# ATmega32_ComServ.net
KiCad netlist of a schematic drawn in Altium Designer
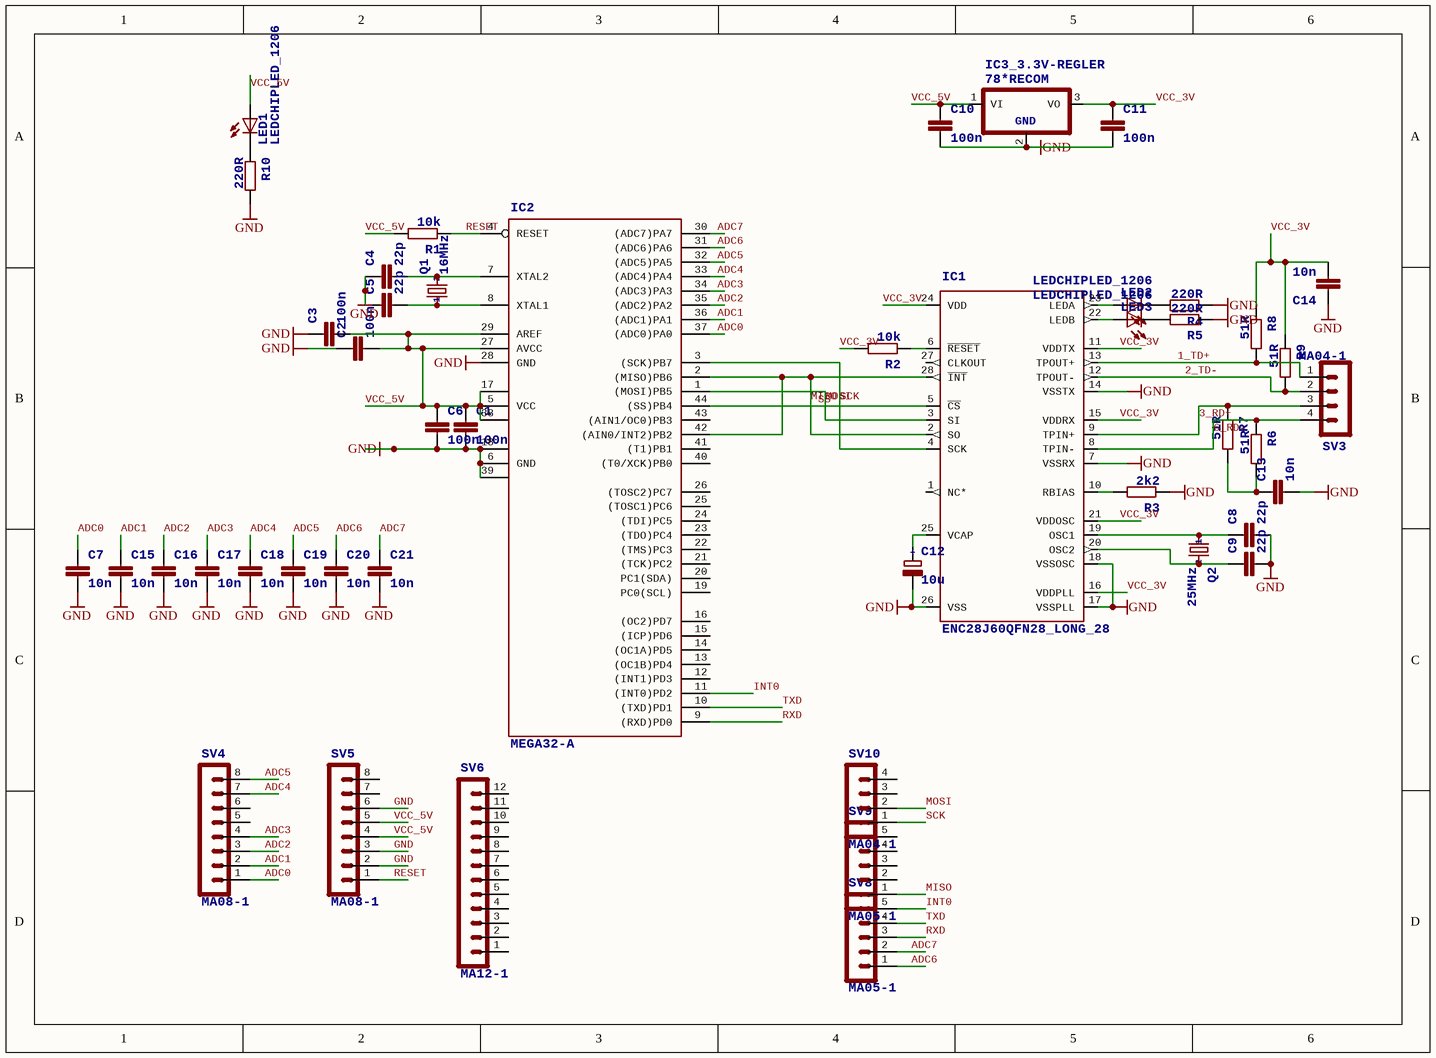
[diagram p0: ATmega32_ComServ.SchDoc]

(export (version "E")
  (design (tool "Eeschema 10.0.6"))
  (components
    (comp (ref "C1")
      (value "100n")
      (footprint "C0805")
      (description "<B>CAPACITOR</B>, European symbol")
      (libsource (lib "rcl") (part "C-EUC0805"))
    )
    (comp (ref "C2")
      (value "100n")
      (footprint "C0805")
      (description "<B>CAPACITOR</B>, European symbol")
      (libsource (lib "") (part "C-EUC0805_1"))
    )
    (comp (ref "C3")
      (value "100n")
      (footprint "C0805")
      (description "<B>CAPACITOR</B>, European symbol")
      (libsource (lib "") (part "C-EUC0805_1"))
    )
    (comp (ref "C4")
      (value "22p")
      (footprint "C0805")
      (description "<B>CAPACITOR</B>, European symbol")
      (libsource (lib "") (part "C-EUC0805_1"))
    )
    (comp (ref "C5")
      (value "22p")
      (footprint "C0805")
      (description "<B>CAPACITOR</B>, European symbol")
      (libsource (lib "") (part "C-EUC0805_1"))
    )
    (comp (ref "C6")
      (value "100n")
      (footprint "C0805")
      (description "<B>CAPACITOR</B>, European symbol")
      (libsource (lib "rcl") (part "C-EUC0805"))
    )
    (comp (ref "C7")
      (value "10n")
      (footprint "C0805")
      (description "<B>CAPACITOR</B>, European symbol")
      (libsource (lib "rcl") (part "C-EUC0805"))
    )
    (comp (ref "C8")
      (value "22p")
      (footprint "C0805")
      (description "<B>CAPACITOR</B>, European symbol")
      (libsource (lib "") (part "C-EUC0805_1"))
    )
    (comp (ref "C9")
      (value "22p")
      (footprint "C0805")
      (description "<B>CAPACITOR</B>, European symbol")
      (libsource (lib "") (part "C-EUC0805_1"))
    )
    (comp (ref "C10")
      (value "100n")
      (footprint "C0805")
      (description "<B>CAPACITOR</B>, European symbol")
      (libsource (lib "rcl") (part "C-EUC0805"))
    )
    (comp (ref "C11")
      (value "100n")
      (footprint "C0805")
      (description "<B>CAPACITOR</B>, European symbol")
      (libsource (lib "rcl") (part "C-EUC0805"))
    )
    (comp (ref "C12")
      (value "10u")
      (footprint "SMC_D")
      (description "<B>POLARIZED CAPACITOR</B>, European symbol")
      (fields (field (name "+") "+"))
      (libsource (lib "rcl") (part "CPOL-EUSMCD"))
    )
    (comp (ref "C13")
      (value "10n")
      (footprint "C0805")
      (description "<B>CAPACITOR</B>, European symbol")
      (libsource (lib "") (part "C-EUC0805_1"))
    )
    (comp (ref "C14")
      (value "10n")
      (footprint "C0805")
      (description "<B>CAPACITOR</B>, European symbol")
      (libsource (lib "") (part "C-EUC0805_2"))
    )
    (comp (ref "C15")
      (value "10n")
      (footprint "C0805")
      (description "<B>CAPACITOR</B>, European symbol")
      (libsource (lib "rcl") (part "C-EUC0805"))
    )
    (comp (ref "C16")
      (value "10n")
      (footprint "C0805")
      (description "<B>CAPACITOR</B>, European symbol")
      (libsource (lib "rcl") (part "C-EUC0805"))
    )
    (comp (ref "C17")
      (value "10n")
      (footprint "C0805")
      (description "<B>CAPACITOR</B>, European symbol")
      (libsource (lib "rcl") (part "C-EUC0805"))
    )
    (comp (ref "C18")
      (value "10n")
      (footprint "C0805")
      (description "<B>CAPACITOR</B>, European symbol")
      (libsource (lib "rcl") (part "C-EUC0805"))
    )
    (comp (ref "C19")
      (value "10n")
      (footprint "C0805")
      (description "<B>CAPACITOR</B>, European symbol")
      (libsource (lib "rcl") (part "C-EUC0805"))
    )
    (comp (ref "C20")
      (value "10n")
      (footprint "C0805")
      (description "<B>CAPACITOR</B>, European symbol")
      (libsource (lib "rcl") (part "C-EUC0805"))
    )
    (comp (ref "C21")
      (value "10n")
      (footprint "C0805")
      (description "<B>CAPACITOR</B>, European symbol")
      (libsource (lib "rcl") (part "C-EUC0805"))
    )
    (comp (ref "IC1")
      (value "ENC28J60QFN28_LONG_28")
      (footprint "QFN28_LONG_ERRLES")
      (libsource (lib "microchip") (part "ENC28J60QFN28_LONG_28"))
    )
    (comp (ref "IC2") (value "MEGA32-A") (footprint "TQFP44") (libsource (lib "atmel") (part "MEGA32-A")))
    (comp (ref "IC3_3.3V-REGLER")
      (value "78*RECOM")
      (footprint "RECOM_3POL")
      (fields (field (name "GND") "GND"))
      (libsource (lib "linear") (part "78*RECOM"))
    )
    (comp (ref "LED1")
      (value "LEDCHIPLED_1206")
      (footprint "CHIPLED_1206")
      (libsource (lib "led") (part "LEDCHIPLED_1206"))
    )
    (comp (ref "LED2")
      (value "LEDCHIPLED_1206")
      (footprint "CHIPLED_1206")
      (libsource (lib "led") (part "LEDCHIPLED_1206"))
    )
    (comp (ref "LED3")
      (value "LEDCHIPLED_1206")
      (footprint "CHIPLED_1206")
      (libsource (lib "led") (part "LEDCHIPLED_1206"))
    )
    (comp (ref "Q1")
      (value "16MHz")
      (footprint "HC49/S")
      (description "<b>CRYSTAL</b>")
      (fields (field (name "1") "1") (field (name "2") "2"))
      (libsource (lib "crystal") (part "CRYSTALHC49S"))
    )
    (comp (ref "Q2")
      (value "25MHz")
      (footprint "HC49/S")
      (description "<b>CRYSTAL</b>")
      (fields (field (name "1") "1") (field (name "2") "2"))
      (libsource (lib "crystal") (part "CRYSTALHC49S"))
    )
    (comp (ref "R1")
      (value "10k")
      (footprint "R1206")
      (description "<B>RESISTOR</B>, European symbol")
      (libsource (lib "rcl") (part "R-EU_R1206"))
    )
    (comp (ref "R2")
      (value "10k")
      (footprint "R1206")
      (description "<B>RESISTOR</B>, European symbol")
      (libsource (lib "rcl") (part "R-EU_R1206"))
    )
    (comp (ref "R3")
      (value "2k2")
      (footprint "R1206")
      (description "<B>RESISTOR</B>, European symbol")
      (libsource (lib "rcl") (part "R-EU_R1206"))
    )
    (comp (ref "R4")
      (value "220R")
      (footprint "R1206")
      (description "<B>RESISTOR</B>, European symbol")
      (libsource (lib "rcl") (part "R-EU_R1206"))
    )
    (comp (ref "R5")
      (value "220R")
      (footprint "R1206")
      (description "<B>RESISTOR</B>, European symbol")
      (libsource (lib "rcl") (part "R-EU_R1206"))
    )
    (comp (ref "R6")
      (value "51R")
      (footprint "R0805")
      (description "<B>RESISTOR</B>, European symbol")
      (libsource (lib "rcl") (part "R-EU_R0805"))
    )
    (comp (ref "R7")
      (value "51R")
      (footprint "R1206")
      (description "<B>RESISTOR</B>, European symbol")
      (libsource (lib "rcl") (part "R-EU_R1206"))
    )
    (comp (ref "R8")
      (value "51R")
      (footprint "R0805")
      (description "<B>RESISTOR</B>, European symbol")
      (libsource (lib "rcl") (part "R-EU_R0805"))
    )
    (comp (ref "R9")
      (value "51R")
      (footprint "R0805")
      (description "<B>RESISTOR</B>, European symbol")
      (libsource (lib "rcl") (part "R-EU_R0805"))
    )
    (comp (ref "R10")
      (value "220R")
      (footprint "R1206")
      (description "<B>RESISTOR</B>, European symbol")
      (libsource (lib "rcl") (part "R-EU_R1206"))
    )
    (comp (ref "SV3")
      (value "MA04-1")
      (footprint "MA04-1")
      (description "<b>PIN HEADER</b>")
      (libsource (lib "con-lstb") (part "MA04-1"))
    )
    (comp (ref "SV4")
      (value "MA08-1")
      (footprint "MA08-1")
      (description "<b>PIN HEADER</b>")
      (libsource (lib "con-lstb") (part "MA08-1"))
    )
    (comp (ref "SV5")
      (value "MA08-1")
      (footprint "MA08-1")
      (description "<b>PIN HEADER</b>")
      (libsource (lib "con-lstb") (part "MA08-1"))
    )
    (comp (ref "SV6")
      (value "MA12-1")
      (footprint "MA12-1")
      (description "<b>PIN HEADER</b>")
      (libsource (lib "con-lstb") (part "MA12-1"))
    )
    (comp (ref "SV8")
      (value "MA05-1")
      (footprint "MA05-1")
      (description "<b>PIN HEADER</b>")
      (libsource (lib "con-lstb") (part "MA05-1"))
    )
    (comp (ref "SV9")
      (value "MA05-1")
      (footprint "MA05-1")
      (description "<b>PIN HEADER</b>")
      (libsource (lib "con-lstb") (part "MA05-1"))
    )
    (comp (ref "SV10")
      (value "MA04-1")
      (footprint "MA04-1")
      (description "<b>PIN HEADER</b>")
      (libsource (lib "con-lstb") (part "MA04-1"))
    )
  )
  (nets
    (net (code "1") (name "/1_TD+") (class "Default")
      (node (ref "IC1") (pin "13") (pinfunction "TPOUT+_13") (pintype "output"))
      (node (ref "R8") (pin "2") (pinfunction "2_2") (pintype "passive"))
      (node (ref "SV3") (pin "1") (pinfunction "1_1") (pintype "passive"))
    )
    (net (code "2") (name "/2_TD-") (class "Default")
      (node (ref "IC1") (pin "12") (pinfunction "TPOUT-_12") (pintype "output"))
      (node (ref "R9") (pin "2") (pinfunction "2_2") (pintype "passive"))
      (node (ref "SV3") (pin "2") (pinfunction "2_2") (pintype "passive"))
    )
    (net (code "3") (name "/3_RD+") (class "Default")
      (node (ref "IC1") (pin "9") (pinfunction "TPIN+_9") (pintype "passive"))
      (node (ref "R7") (pin "1") (pinfunction "1_1") (pintype "passive"))
      (node (ref "SV3") (pin "3") (pinfunction "3_3") (pintype "passive"))
    )
    (net (code "4") (name "/6_RD-") (class "Default")
      (node (ref "IC1") (pin "8") (pinfunction "TPIN-_8") (pintype "passive"))
      (node (ref "R6") (pin "1") (pinfunction "1_1") (pintype "passive"))
      (node (ref "SV3") (pin "4") (pinfunction "4_4") (pintype "passive"))
    )
    (net (code "5") (name "/ADC0") (class "Default")
      (node (ref "C7") (pin "1") (pinfunction "1_1") (pintype "passive"))
      (node (ref "IC2") (pin "37") (pinfunction "(ADC0)PA0_37") (pintype "passive"))
      (node (ref "SV4") (pin "1") (pinfunction "1_1") (pintype "passive"))
    )
    (net (code "6") (name "/ADC1") (class "Default")
      (node (ref "C15") (pin "1") (pinfunction "1_1") (pintype "passive"))
      (node (ref "IC2") (pin "36") (pinfunction "(ADC1)PA1_36") (pintype "passive"))
      (node (ref "SV4") (pin "2") (pinfunction "2_2") (pintype "passive"))
    )
    (net (code "7") (name "/ADC2") (class "Default")
      (node (ref "C16") (pin "1") (pinfunction "1_1") (pintype "passive"))
      (node (ref "IC2") (pin "35") (pinfunction "(ADC2)PA2_35") (pintype "passive"))
      (node (ref "SV4") (pin "3") (pinfunction "3_3") (pintype "passive"))
    )
    (net (code "8") (name "/ADC3") (class "Default")
      (node (ref "C17") (pin "1") (pinfunction "1_1") (pintype "passive"))
      (node (ref "IC2") (pin "34") (pinfunction "(ADC3)PA3_34") (pintype "passive"))
      (node (ref "SV4") (pin "4") (pinfunction "4_4") (pintype "passive"))
    )
    (net (code "9") (name "/ADC4") (class "Default")
      (node (ref "C18") (pin "1") (pinfunction "1_1") (pintype "passive"))
      (node (ref "IC2") (pin "33") (pinfunction "(ADC4)PA4_33") (pintype "passive"))
      (node (ref "SV4") (pin "7") (pinfunction "7_7") (pintype "passive"))
    )
    (net (code "10") (name "/ADC5") (class "Default")
      (node (ref "C19") (pin "1") (pinfunction "1_1") (pintype "passive"))
      (node (ref "IC2") (pin "32") (pinfunction "(ADC5)PA5_32") (pintype "passive"))
      (node (ref "SV4") (pin "8") (pinfunction "8_8") (pintype "passive"))
    )
    (net (code "11") (name "/ADC6") (class "Default")
      (node (ref "C20") (pin "1") (pinfunction "1_1") (pintype "passive"))
      (node (ref "IC2") (pin "31") (pinfunction "(ADC6)PA6_31") (pintype "passive"))
      (node (ref "SV8") (pin "1") (pinfunction "1_1") (pintype "passive"))
    )
    (net (code "12") (name "/ADC7") (class "Default")
      (node (ref "C21") (pin "1") (pinfunction "1_1") (pintype "passive"))
      (node (ref "IC2") (pin "30") (pinfunction "(ADC7)PA7_30") (pintype "passive"))
      (node (ref "SV8") (pin "2") (pinfunction "2_2") (pintype "passive"))
    )
    (net (code "13") (name "/INT0") (class "Default")
      (node (ref "IC2") (pin "11") (pinfunction "(INT0)PD2_11") (pintype "passive"))
      (node (ref "SV8") (pin "5") (pinfunction "5_5") (pintype "passive"))
    )
    (net (code "14") (name "/MISO") (class "Default")
      (node (ref "IC1") (pin "2") (pinfunction "SO_2") (pintype "output"))
      (node (ref "IC1") (pin "28") (pinfunction "~{INT}_28") (pintype "output"))
      (node (ref "IC2") (pin "2") (pinfunction "(MISO)PB6_2") (pintype "passive"))
      (node (ref "IC2") (pin "42") (pinfunction "(AIN0/INT2)PB2_42") (pintype "passive"))
      (node (ref "SV9") (pin "1") (pinfunction "1_1") (pintype "passive"))
    )
    (net (code "15") (name "/MOSI") (class "Default")
      (node (ref "IC1") (pin "3") (pinfunction "SI_3") (pintype "passive"))
      (node (ref "IC2") (pin "1") (pinfunction "(MOSI)PB5_1") (pintype "passive"))
      (node (ref "SV10") (pin "2") (pinfunction "2_2") (pintype "passive"))
    )
    (net (code "16") (name "/RESET") (class "Default")
      (node (ref "IC2") (pin "4") (pinfunction "RESET_4") (pintype "passive"))
      (node (ref "R1") (pin "1") (pinfunction "1_1") (pintype "passive"))
      (node (ref "SV5") (pin "1") (pinfunction "1_1") (pintype "passive"))
    )
    (net (code "17") (name "/RXD") (class "Default")
      (node (ref "IC2") (pin "9") (pinfunction "(RXD)PD0_9") (pintype "passive"))
      (node (ref "SV8") (pin "3") (pinfunction "3_3") (pintype "passive"))
    )
    (net (code "18") (name "/SCK") (class "Default")
      (node (ref "IC1") (pin "4") (pinfunction "SCK_4") (pintype "passive"))
      (node (ref "IC2") (pin "3") (pinfunction "(SCK)PB7_3") (pintype "passive"))
      (node (ref "SV10") (pin "1") (pinfunction "1_1") (pintype "passive"))
    )
    (net (code "19") (name "/SS") (class "Default")
      (node (ref "IC1") (pin "5") (pinfunction "~{CS}_5") (pintype "passive"))
      (node (ref "IC2") (pin "44") (pinfunction "(SS)PB4_44") (pintype "passive"))
    )
    (net (code "20") (name "/TXD") (class "Default")
      (node (ref "IC2") (pin "10") (pinfunction "(TXD)PD1_10") (pintype "passive"))
      (node (ref "SV8") (pin "4") (pinfunction "4_4") (pintype "passive"))
    )
    (net (code "21") (name "/VCC_3V") (class "Default")
      (node (ref "C11") (pin "1") (pinfunction "1_1") (pintype "passive"))
      (node (ref "C14") (pin "2") (pinfunction "2_2") (pintype "passive"))
      (node (ref "IC1") (pin "11") (pinfunction "VDDTX_11") (pintype "passive"))
      (node (ref "IC1") (pin "15") (pinfunction "VDDRX_15") (pintype "passive"))
      (node (ref "IC1") (pin "16") (pinfunction "VDDPLL_16") (pintype "passive"))
      (node (ref "IC1") (pin "21") (pinfunction "VDDOSC_21") (pintype "passive"))
      (node (ref "IC1") (pin "24") (pinfunction "VDD_24") (pintype "passive"))
      (node (ref "IC3_3.3V-REGLER") (pin "3") (pinfunction "VO_3") (pintype "passive"))
      (node (ref "R2") (pin "2") (pinfunction "2_2") (pintype "passive"))
      (node (ref "R8") (pin "1") (pinfunction "1_1") (pintype "passive"))
      (node (ref "R9") (pin "1") (pinfunction "1_1") (pintype "passive"))
    )
    (net (code "22") (name "/VCC_5V") (class "Default")
      (node (ref "C1") (pin "1") (pinfunction "1_1") (pintype "passive"))
      (node (ref "C10") (pin "1") (pinfunction "1_1") (pintype "passive"))
      (node (ref "C2") (pin "2") (pinfunction "2_2") (pintype "passive"))
      (node (ref "C3") (pin "2") (pinfunction "2_2") (pintype "passive"))
      (node (ref "C6") (pin "1") (pinfunction "1_1") (pintype "passive"))
      (node (ref "IC2") (pin "17") (pinfunction "VCC1_17") (pintype "power_in"))
      (node (ref "IC2") (pin "27") (pinfunction "AVCC_27") (pintype "power_in"))
      (node (ref "IC2") (pin "29") (pinfunction "AREF_29") (pintype "passive"))
      (node (ref "IC2") (pin "38") (pinfunction "VCC2_38") (pintype "power_in"))
      (node (ref "IC2") (pin "5") (pinfunction "VCC_5") (pintype "power_in"))
      (node (ref "IC3_3.3V-REGLER") (pin "1") (pinfunction "VI_1") (pintype "passive"))
      (node (ref "LED1") (pin "A") (pinfunction "A_A") (pintype "passive"))
      (node (ref "R1") (pin "2") (pinfunction "2_2") (pintype "passive"))
      (node (ref "SV5") (pin "4") (pinfunction "4_4") (pintype "passive"))
      (node (ref "SV5") (pin "5") (pinfunction "5_5") (pintype "passive"))
    )
    (net (code "23") (name "GND") (class "Default")
      (node (ref "C1") (pin "2") (pinfunction "2_2") (pintype "passive"))
      (node (ref "C10") (pin "2") (pinfunction "2_2") (pintype "passive"))
      (node (ref "C11") (pin "2") (pinfunction "2_2") (pintype "passive"))
      (node (ref "C12") (pin "-") (pinfunction "-_-") (pintype "passive"))
      (node (ref "C13") (pin "2") (pinfunction "2_2") (pintype "passive"))
      (node (ref "C14") (pin "1") (pinfunction "1_1") (pintype "passive"))
      (node (ref "C15") (pin "2") (pinfunction "2_2") (pintype "passive"))
      (node (ref "C16") (pin "2") (pinfunction "2_2") (pintype "passive"))
      (node (ref "C17") (pin "2") (pinfunction "2_2") (pintype "passive"))
      (node (ref "C18") (pin "2") (pinfunction "2_2") (pintype "passive"))
      (node (ref "C19") (pin "2") (pinfunction "2_2") (pintype "passive"))
      (node (ref "C2") (pin "1") (pinfunction "1_1") (pintype "passive"))
      (node (ref "C20") (pin "2") (pinfunction "2_2") (pintype "passive"))
      (node (ref "C21") (pin "2") (pinfunction "2_2") (pintype "passive"))
      (node (ref "C3") (pin "1") (pinfunction "1_1") (pintype "passive"))
      (node (ref "C4") (pin "1") (pinfunction "1_1") (pintype "passive"))
      (node (ref "C5") (pin "1") (pinfunction "1_1") (pintype "passive"))
      (node (ref "C6") (pin "2") (pinfunction "2_2") (pintype "passive"))
      (node (ref "C7") (pin "2") (pinfunction "2_2") (pintype "passive"))
      (node (ref "C8") (pin "2") (pinfunction "2_2") (pintype "passive"))
      (node (ref "C9") (pin "2") (pinfunction "2_2") (pintype "passive"))
      (node (ref "IC1") (pin "14") (pinfunction "VSSTX_14") (pintype "passive"))
      (node (ref "IC1") (pin "17") (pinfunction "VSSPLL_17") (pintype "passive"))
      (node (ref "IC1") (pin "18") (pinfunction "VSSOSC_18") (pintype "passive"))
      (node (ref "IC1") (pin "26") (pinfunction "VSS_26") (pintype "passive"))
      (node (ref "IC1") (pin "7") (pinfunction "VSSRX_7") (pintype "passive"))
      (node (ref "IC2") (pin "18") (pinfunction "GND1_18") (pintype "power_in"))
      (node (ref "IC2") (pin "28") (pinfunction "GND_28") (pintype "power_in"))
      (node (ref "IC2") (pin "39") (pinfunction "GND2_39") (pintype "power_in"))
      (node (ref "IC2") (pin "6") (pinfunction "GND_6") (pintype "power_in"))
      (node (ref "IC3_3.3V-REGLER") (pin "2") (pinfunction "GND_2") (pintype "passive"))
      (node (ref "R10") (pin "2") (pinfunction "2_2") (pintype "passive"))
      (node (ref "R3") (pin "1") (pinfunction "1_1") (pintype "passive"))
      (node (ref "R4") (pin "1") (pinfunction "1_1") (pintype "passive"))
      (node (ref "R5") (pin "1") (pinfunction "1_1") (pintype "passive"))
      (node (ref "SV5") (pin "2") (pinfunction "2_2") (pintype "passive"))
      (node (ref "SV5") (pin "3") (pinfunction "3_3") (pintype "passive"))
      (node (ref "SV5") (pin "6") (pinfunction "6_6") (pintype "passive"))
    )
    (net (code "24") (name "Net-(C13-Pad1)") (class "Default")
      (node (ref "C13") (pin "1") (pinfunction "1_1") (pintype "passive"))
      (node (ref "R6") (pin "2") (pinfunction "2_2") (pintype "passive"))
      (node (ref "R7") (pin "2") (pinfunction "2_2") (pintype "passive"))
    )
    (net (code "25") (name "Net-(IC1-LEDA)") (class "Default")
      (node (ref "IC1") (pin "23") (pinfunction "LEDA_23") (pintype "output"))
      (node (ref "LED2") (pin "A") (pinfunction "A_A") (pintype "passive"))
    )
    (net (code "26") (name "Net-(IC1-LEDB)") (class "Default")
      (node (ref "IC1") (pin "22") (pinfunction "LEDB_22") (pintype "output"))
      (node (ref "LED3") (pin "A") (pinfunction "A_A") (pintype "passive"))
    )
    (net (code "27") (name "Net-(IC1-OSC1)") (class "Default")
      (node (ref "C8") (pin "1") (pinfunction "1_1") (pintype "passive"))
      (node (ref "IC1") (pin "19") (pinfunction "OSC1_19") (pintype "passive"))
      (node (ref "Q2") (pin "1") (pinfunction "1_1") (pintype "passive"))
    )
    (net (code "28") (name "Net-(IC1-OSC2)") (class "Default")
      (node (ref "C9") (pin "1") (pinfunction "1_1") (pintype "passive"))
      (node (ref "IC1") (pin "20") (pinfunction "OSC2_20") (pintype "output"))
      (node (ref "Q2") (pin "2") (pinfunction "2_2") (pintype "passive"))
    )
    (net (code "29") (name "Net-(IC1-RBIAS)") (class "Default")
      (node (ref "IC1") (pin "10") (pinfunction "RBIAS_10") (pintype "passive"))
      (node (ref "R3") (pin "2") (pinfunction "2_2") (pintype "passive"))
    )
    (net (code "30") (name "Net-(IC1-VCAP)") (class "Default")
      (node (ref "C12") (pin "+") (pinfunction "+_+") (pintype "passive"))
      (node (ref "IC1") (pin "25") (pinfunction "VCAP_25") (pintype "passive"))
    )
    (net (code "31") (name "Net-(IC1-~{RESET})") (class "Default")
      (node (ref "IC1") (pin "6") (pinfunction "~{RESET}_6") (pintype "passive"))
      (node (ref "R2") (pin "1") (pinfunction "1_1") (pintype "passive"))
    )
    (net (code "32") (name "Net-(IC2-XTAL1)") (class "Default")
      (node (ref "C5") (pin "2") (pinfunction "2_2") (pintype "passive"))
      (node (ref "IC2") (pin "8") (pinfunction "XTAL1_8") (pintype "passive"))
      (node (ref "Q1") (pin "1") (pinfunction "1_1") (pintype "passive"))
    )
    (net (code "33") (name "Net-(IC2-XTAL2)") (class "Default")
      (node (ref "C4") (pin "2") (pinfunction "2_2") (pintype "passive"))
      (node (ref "IC2") (pin "7") (pinfunction "XTAL2_7") (pintype "passive"))
      (node (ref "Q1") (pin "2") (pinfunction "2_2") (pintype "passive"))
    )
    (net (code "34") (name "Net-(LED1-PadC)") (class "Default")
      (node (ref "LED1") (pin "C") (pinfunction "C_C") (pintype "passive"))
      (node (ref "R10") (pin "1") (pinfunction "1_1") (pintype "passive"))
    )
    (net (code "35") (name "Net-(LED2-PadC)") (class "Default")
      (node (ref "LED2") (pin "C") (pinfunction "C_C") (pintype "passive"))
      (node (ref "R4") (pin "2") (pinfunction "2_2") (pintype "passive"))
    )
    (net (code "36") (name "Net-(LED3-PadC)") (class "Default")
      (node (ref "LED3") (pin "C") (pinfunction "C_C") (pintype "passive"))
      (node (ref "R5") (pin "2") (pinfunction "2_2") (pintype "passive"))
    )
    (net (code "37") (name "unconnected-(IC1-CLKOUT-Pad27)") (class "Default")
      (node (ref "IC1") (pin "27") (pinfunction "CLKOUT_27") (pintype "output"))
    )
    (net (code "38") (name "unconnected-(IC1-NC*-Pad1)") (class "Default")
      (node (ref "IC1") (pin "1") (pinfunction "NC*_1") (pintype "output"))
    )
    (net (code "39") (name "unconnected-(IC2-(AIN1{slash}OC0)PB3-Pad43)") (class "Default")
      (node (ref "IC2") (pin "43") (pinfunction "(AIN1/OC0)PB3_43") (pintype "passive"))
    )
    (net (code "40") (name "unconnected-(IC2-(ICP)PD6-Pad15)") (class "Default")
      (node (ref "IC2") (pin "15") (pinfunction "(ICP)PD6_15") (pintype "passive"))
    )
    (net (code "41") (name "unconnected-(IC2-(INT1)PD3-Pad12)") (class "Default")
      (node (ref "IC2") (pin "12") (pinfunction "(INT1)PD3_12") (pintype "passive"))
    )
    (net (code "42") (name "unconnected-(IC2-(OC1A)PD5-Pad14)") (class "Default")
      (node (ref "IC2") (pin "14") (pinfunction "(OC1A)PD5_14") (pintype "passive"))
    )
    (net (code "43") (name "unconnected-(IC2-(OC1B)PD4-Pad13)") (class "Default")
      (node (ref "IC2") (pin "13") (pinfunction "(OC1B)PD4_13") (pintype "passive"))
    )
    (net (code "44") (name "unconnected-(IC2-(OC2)PD7-Pad16)") (class "Default")
      (node (ref "IC2") (pin "16") (pinfunction "(OC2)PD7_16") (pintype "passive"))
    )
    (net (code "45") (name "unconnected-(IC2-(T0{slash}XCK)PB0-Pad40)") (class "Default")
      (node (ref "IC2") (pin "40") (pinfunction "(T0/XCK)PB0_40") (pintype "passive"))
    )
    (net (code "46") (name "unconnected-(IC2-(T1)PB1-Pad41)") (class "Default")
      (node (ref "IC2") (pin "41") (pinfunction "(T1)PB1_41") (pintype "passive"))
    )
    (net (code "47") (name "unconnected-(IC2-(TCK)PC2-Pad21)") (class "Default")
      (node (ref "IC2") (pin "21") (pinfunction "(TCK)PC2_21") (pintype "passive"))
    )
    (net (code "48") (name "unconnected-(IC2-(TDI)PC5-Pad24)") (class "Default")
      (node (ref "IC2") (pin "24") (pinfunction "(TDI)PC5_24") (pintype "passive"))
    )
    (net (code "49") (name "unconnected-(IC2-(TDO)PC4-Pad23)") (class "Default")
      (node (ref "IC2") (pin "23") (pinfunction "(TDO)PC4_23") (pintype "passive"))
    )
    (net (code "50") (name "unconnected-(IC2-(TMS)PC3-Pad22)") (class "Default")
      (node (ref "IC2") (pin "22") (pinfunction "(TMS)PC3_22") (pintype "passive"))
    )
    (net (code "51") (name "unconnected-(IC2-(TOSC1)PC6-Pad25)") (class "Default")
      (node (ref "IC2") (pin "25") (pinfunction "(TOSC1)PC6_25") (pintype "passive"))
    )
    (net (code "52") (name "unconnected-(IC2-(TOSC2)PC7-Pad26)") (class "Default")
      (node (ref "IC2") (pin "26") (pinfunction "(TOSC2)PC7_26") (pintype "passive"))
    )
    (net (code "53") (name "unconnected-(IC2-PC0(SCL)-Pad19)") (class "Default")
      (node (ref "IC2") (pin "19") (pinfunction "PC0(SCL)_19") (pintype "passive"))
    )
    (net (code "54") (name "unconnected-(IC2-PC1(SDA)-Pad20)") (class "Default")
      (node (ref "IC2") (pin "20") (pinfunction "PC1(SDA)_20") (pintype "passive"))
    )
    (net (code "55") (name "unconnected-(SV4-Pad5)") (class "Default")
      (node (ref "SV4") (pin "5") (pinfunction "5_5") (pintype "passive"))
    )
    (net (code "56") (name "unconnected-(SV4-Pad6)") (class "Default")
      (node (ref "SV4") (pin "6") (pinfunction "6_6") (pintype "passive"))
    )
    (net (code "57") (name "unconnected-(SV5-Pad7)") (class "Default")
      (node (ref "SV5") (pin "7") (pinfunction "7_7") (pintype "passive"))
    )
    (net (code "58") (name "unconnected-(SV5-Pad8)") (class "Default")
      (node (ref "SV5") (pin "8") (pinfunction "8_8") (pintype "passive"))
    )
    (net (code "59") (name "unconnected-(SV6-Pad1)") (class "Default")
      (node (ref "SV6") (pin "1") (pinfunction "1_1") (pintype "passive"))
    )
    (net (code "60") (name "unconnected-(SV6-Pad2)") (class "Default")
      (node (ref "SV6") (pin "2") (pinfunction "2_2") (pintype "passive"))
    )
    (net (code "61") (name "unconnected-(SV6-Pad3)") (class "Default")
      (node (ref "SV6") (pin "3") (pinfunction "3_3") (pintype "passive"))
    )
    (net (code "62") (name "unconnected-(SV6-Pad4)") (class "Default")
      (node (ref "SV6") (pin "4") (pinfunction "4_4") (pintype "passive"))
    )
    (net (code "63") (name "unconnected-(SV6-Pad5)") (class "Default")
      (node (ref "SV6") (pin "5") (pinfunction "5_5") (pintype "passive"))
    )
    (net (code "64") (name "unconnected-(SV6-Pad6)") (class "Default")
      (node (ref "SV6") (pin "6") (pinfunction "6_6") (pintype "passive"))
    )
    (net (code "65") (name "unconnected-(SV6-Pad7)") (class "Default")
      (node (ref "SV6") (pin "7") (pinfunction "7_7") (pintype "passive"))
    )
    (net (code "66") (name "unconnected-(SV6-Pad8)") (class "Default")
      (node (ref "SV6") (pin "8") (pinfunction "8_8") (pintype "passive"))
    )
    (net (code "67") (name "unconnected-(SV6-Pad9)") (class "Default")
      (node (ref "SV6") (pin "9") (pinfunction "9_9") (pintype "passive"))
    )
    (net (code "68") (name "unconnected-(SV6-Pad10)") (class "Default")
      (node (ref "SV6") (pin "10") (pinfunction "10_10") (pintype "passive"))
    )
    (net (code "69") (name "unconnected-(SV6-Pad11)") (class "Default")
      (node (ref "SV6") (pin "11") (pinfunction "11_11") (pintype "passive"))
    )
    (net (code "70") (name "unconnected-(SV6-Pad12)") (class "Default")
      (node (ref "SV6") (pin "12") (pinfunction "12_12") (pintype "passive"))
    )
    (net (code "71") (name "unconnected-(SV9-Pad2)") (class "Default")
      (node (ref "SV9") (pin "2") (pinfunction "2_2") (pintype "passive"))
    )
    (net (code "72") (name "unconnected-(SV9-Pad3)") (class "Default")
      (node (ref "SV9") (pin "3") (pinfunction "3_3") (pintype "passive"))
    )
    (net (code "73") (name "unconnected-(SV9-Pad4)") (class "Default")
      (node (ref "SV9") (pin "4") (pinfunction "4_4") (pintype "passive"))
    )
    (net (code "74") (name "unconnected-(SV9-Pad5)") (class "Default")
      (node (ref "SV9") (pin "5") (pinfunction "5_5") (pintype "passive"))
    )
    (net (code "75") (name "unconnected-(SV10-Pad3)") (class "Default")
      (node (ref "SV10") (pin "3") (pinfunction "3_3") (pintype "passive"))
    )
    (net (code "76") (name "unconnected-(SV10-Pad4)") (class "Default")
      (node (ref "SV10") (pin "4") (pinfunction "4_4") (pintype "passive"))
    )
  )
)
